# TRS_NANO.net
KiCad netlist of a schematic drawn in EAGLE
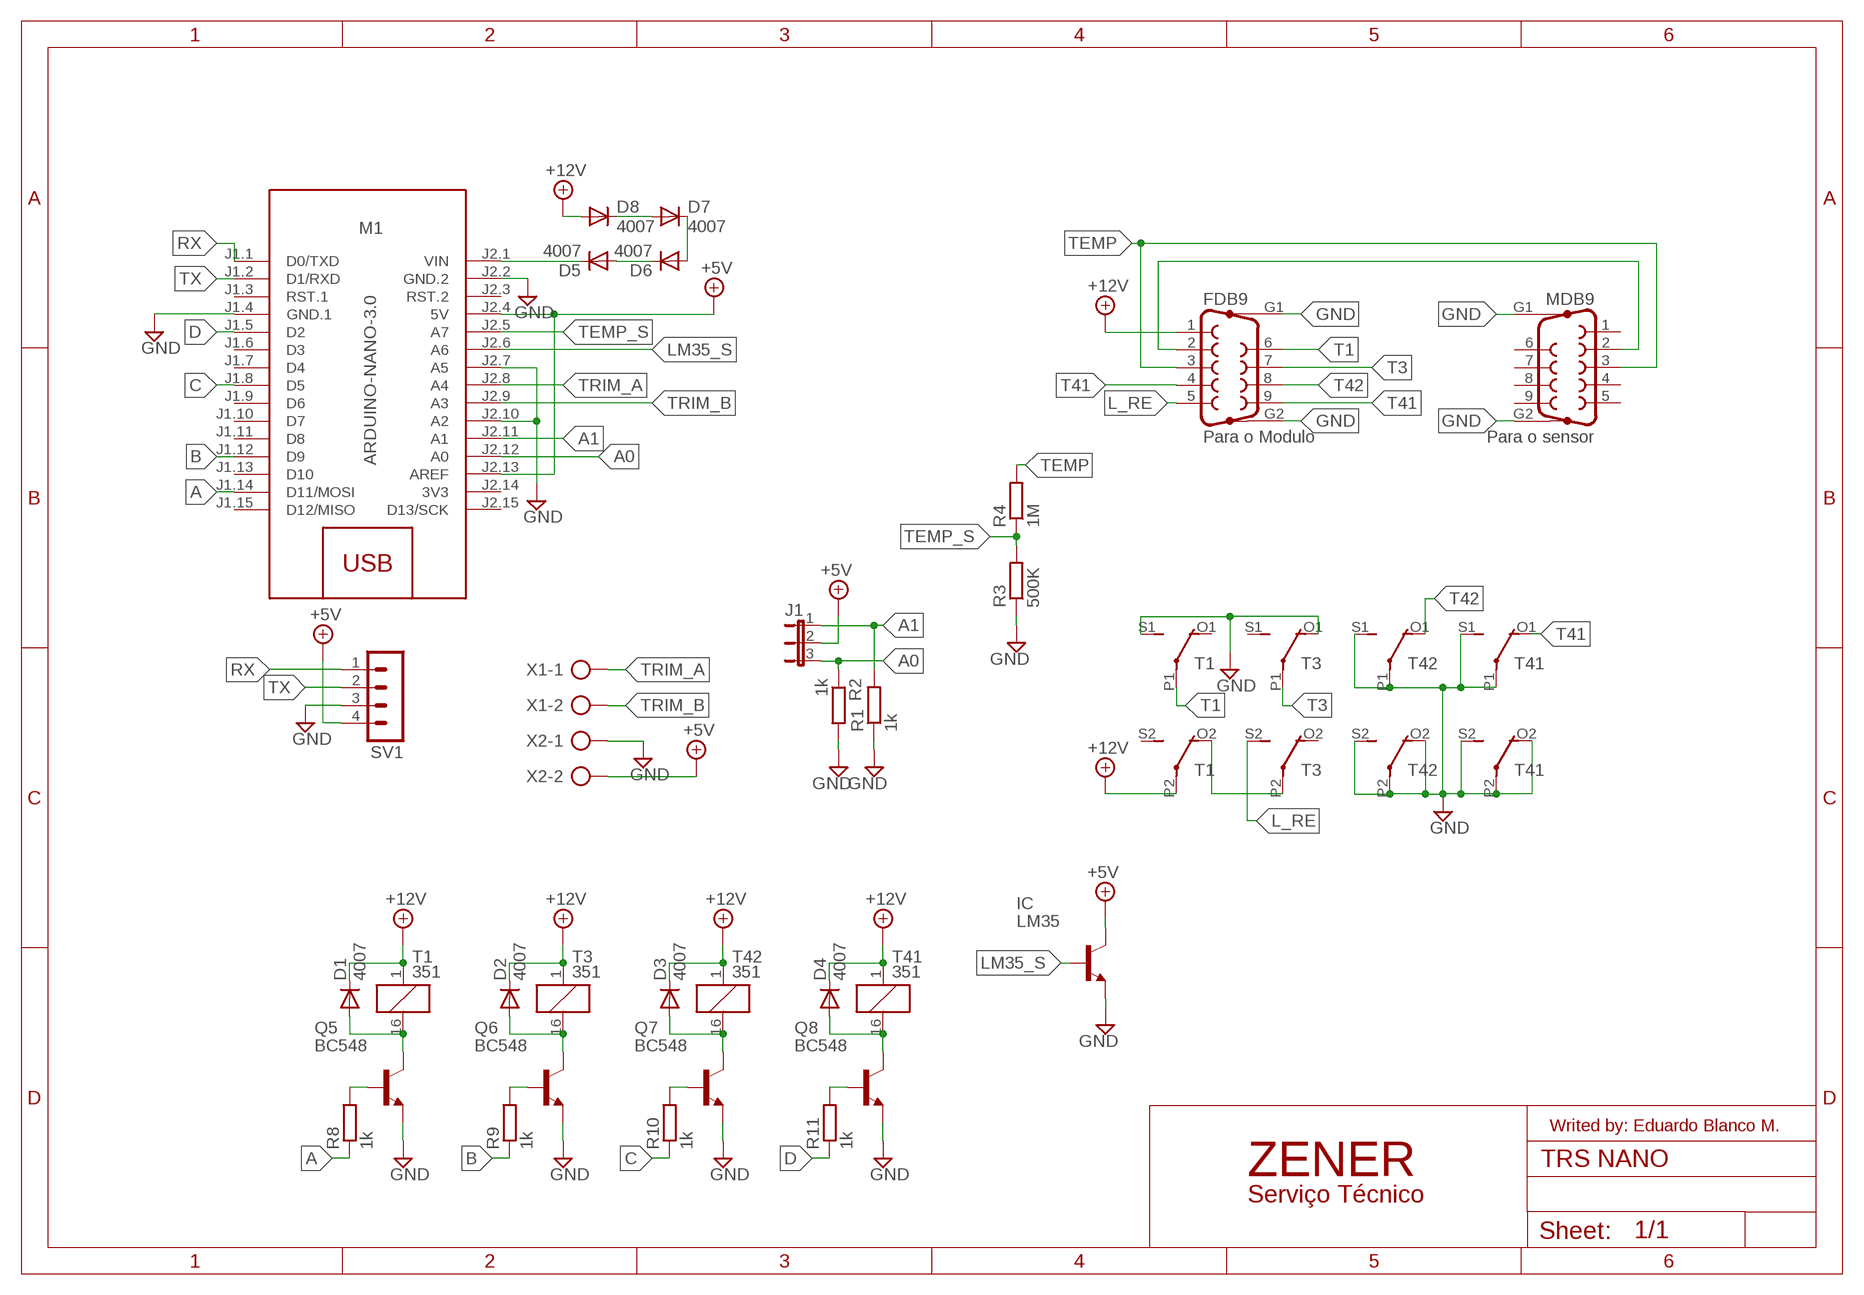
[diagram p0: schematic, sheet 1]

(export (version "E")
  (design (tool "Eeschema 10.0.6"))
  (components
    (comp (ref "D1")
      (value "4007")
      (footprint "eagle-import:D-7.5")
      (libsource (lib "eagle-import") (part "DIODE-D-7.5"))
    )
    (comp (ref "D2")
      (value "4007")
      (footprint "eagle-import:D-7.5")
      (libsource (lib "eagle-import") (part "DIODE-D-7.5"))
    )
    (comp (ref "D3")
      (value "4007")
      (footprint "eagle-import:D-7.5")
      (libsource (lib "eagle-import") (part "DIODE-D-7.5"))
    )
    (comp (ref "D4")
      (value "4007")
      (footprint "eagle-import:D-7.5")
      (libsource (lib "eagle-import") (part "DIODE-D-7.5"))
    )
    (comp (ref "D5")
      (value "4007")
      (footprint "eagle-import:D-7.5")
      (libsource (lib "eagle-import") (part "DIODE-D-7.5"))
    )
    (comp (ref "D6")
      (value "4007")
      (footprint "eagle-import:D-7.5")
      (libsource (lib "eagle-import") (part "DIODE-D-7.5"))
    )
    (comp (ref "D7")
      (value "4007")
      (footprint "eagle-import:D-7.5")
      (libsource (lib "eagle-import") (part "DIODE-D-7.5"))
    )
    (comp (ref "D8")
      (value "4007")
      (footprint "eagle-import:D-7.5")
      (libsource (lib "eagle-import") (part "DIODE-D-7.5"))
    )
    (comp (ref "FDB9")
      (value "Para o Modulo")
      (footprint "eagle-import:F09HP")
      (libsource (lib "eagle-import") (part "F09HP"))
    )
    (comp (ref "IC")
      (value "LM35")
      (footprint "eagle-import:TO92-EBC")
      (libsource (lib "eagle-import") (part "BC548"))
    )
    (comp (ref "J1")
      (value "JP2W")
      (footprint "eagle-import:JP2W")
      (libsource (lib "eagle-import") (part "JP2W"))
    )
    (comp (ref "M1")
      (value "ARDUINO-NANO-3.0")
      (footprint "eagle-import:ARDUINO-NANO-3.0")
      (libsource (lib "eagle-import") (part "ARDUINO-NANO-3.0"))
    )
    (comp (ref "MDB9")
      (value "Para o sensor")
      (footprint "eagle-import:F09HP")
      (libsource (lib "eagle-import") (part "F09HP"))
    )
    (comp (ref "Q5")
      (value "BC548")
      (footprint "eagle-import:TO92-EBC")
      (libsource (lib "eagle-import") (part "BC548"))
    )
    (comp (ref "Q6")
      (value "BC548")
      (footprint "eagle-import:TO92-EBC")
      (libsource (lib "eagle-import") (part "BC548"))
    )
    (comp (ref "Q7")
      (value "BC548")
      (footprint "eagle-import:TO92-EBC")
      (libsource (lib "eagle-import") (part "BC548"))
    )
    (comp (ref "Q8")
      (value "BC548")
      (footprint "eagle-import:TO92-EBC")
      (libsource (lib "eagle-import") (part "BC548"))
    )
    (comp (ref "R1")
      (value "1k")
      (footprint "eagle-import:0207_10")
      (libsource (lib "eagle-import") (part "R-EU_0207/10"))
    )
    (comp (ref "R2")
      (value "1k")
      (footprint "eagle-import:0207_7")
      (libsource (lib "eagle-import") (part "R-EU_0207/7"))
    )
    (comp (ref "R3")
      (value "500K")
      (footprint "eagle-import:0207_7")
      (libsource (lib "eagle-import") (part "R-EU_0207/7"))
    )
    (comp (ref "R4")
      (value "1M")
      (footprint "eagle-import:0207_15")
      (libsource (lib "eagle-import") (part "R-EU_0207/15"))
    )
    (comp (ref "R8")
      (value "1k")
      (footprint "eagle-import:0207_5V")
      (libsource (lib "eagle-import") (part "R-EU_0207/5V"))
    )
    (comp (ref "R9")
      (value "1k")
      (footprint "eagle-import:0207_5V")
      (libsource (lib "eagle-import") (part "R-EU_0207/5V"))
    )
    (comp (ref "R10")
      (value "1k")
      (footprint "eagle-import:0207_5V")
      (libsource (lib "eagle-import") (part "R-EU_0207/5V"))
    )
    (comp (ref "R11")
      (value "1k")
      (footprint "eagle-import:0207_5V")
      (libsource (lib "eagle-import") (part "R-EU_0207/5V"))
    )
    (comp (ref "SV1")
      (value "MA04-1")
      (footprint "eagle-import:MA04-1")
      (libsource (lib "eagle-import") (part "MA04-1"))
    )
    (comp (ref "T1")
      (value "351")
      (footprint "eagle-import:351")
      (libsource (lib "eagle-import") (part "351"))
    )
    (comp (ref "T3")
      (value "351")
      (footprint "eagle-import:351")
      (libsource (lib "eagle-import") (part "351"))
    )
    (comp (ref "T41")
      (value "351")
      (footprint "eagle-import:351")
      (libsource (lib "eagle-import") (part "351"))
    )
    (comp (ref "T42")
      (value "351")
      (footprint "eagle-import:351")
      (libsource (lib "eagle-import") (part "351"))
    )
    (comp (ref "X1")
      (value "AK500/2")
      (footprint "eagle-import:AK500_2")
      (libsource (lib "eagle-import") (part "AK500/2"))
    )
    (comp (ref "X2")
      (value "AK500/2")
      (footprint "eagle-import:AK500_2")
      (libsource (lib "eagle-import") (part "AK500/2"))
    )
  )
  (nets
    (net (code "1") (name "+5V") (class "Default")
      (node (ref "IC") (pin "C") (pinfunction "C_C") (pintype "passive"))
      (node (ref "J1") (pin "2") (pinfunction "2_2") (pintype "passive"))
      (node (ref "M1") (pin "J2.13") (pinfunction "AREF_J2.13") (pintype "bidirectional"))
      (node (ref "M1") (pin "J2.4") (pinfunction "5V_J2.4") (pintype "power_in"))
      (node (ref "SV1") (pin "4") (pinfunction "4_4") (pintype "passive"))
      (node (ref "X2") (pin "2") (pinfunction "KL_2") (pintype "passive"))
    )
    (net (code "2") (name "+12V") (class "Default")
      (node (ref "D1") (pin "C") (pinfunction "C_C") (pintype "passive"))
      (node (ref "D2") (pin "C") (pinfunction "C_C") (pintype "passive"))
      (node (ref "D3") (pin "C") (pinfunction "C_C") (pintype "passive"))
      (node (ref "D4") (pin "C") (pinfunction "C_C") (pintype "passive"))
      (node (ref "D8") (pin "A") (pinfunction "A_A") (pintype "passive"))
      (node (ref "FDB9") (pin "1") (pinfunction "1_1") (pintype "passive"))
      (node (ref "T1") (pin "1") (pinfunction "1_1") (pintype "passive"))
      (node (ref "T1") (pin "P2") (pinfunction "P_P2") (pintype "passive"))
      (node (ref "T3") (pin "1") (pinfunction "1_1") (pintype "passive"))
      (node (ref "T41") (pin "1") (pinfunction "1_1") (pintype "passive"))
      (node (ref "T42") (pin "1") (pinfunction "1_1") (pintype "passive"))
    )
    (net (code "3") (name "/3V3") (class "Default")
      (node (ref "M1") (pin "J2.14") (pinfunction "3V3_J2.14") (pintype "power_in"))
    )
    (net (code "4") (name "A") (class "Default")
      (node (ref "M1") (pin "J1.14") (pinfunction "D11/MOSI_J1.14") (pintype "bidirectional"))
      (node (ref "R8") (pin "1") (pinfunction "1_1") (pintype "passive"))
    )
    (net (code "5") (name "A0") (class "Default")
      (node (ref "J1") (pin "3") (pinfunction "3_3") (pintype "passive"))
      (node (ref "M1") (pin "J2.12") (pinfunction "A0_J2.12") (pintype "bidirectional"))
      (node (ref "R2") (pin "1") (pinfunction "1_1") (pintype "passive"))
    )
    (net (code "6") (name "A1") (class "Default")
      (node (ref "J1") (pin "1") (pinfunction "1_1") (pintype "passive"))
      (node (ref "M1") (pin "J2.11") (pinfunction "A1_J2.11") (pintype "bidirectional"))
      (node (ref "R1") (pin "2") (pinfunction "2_2") (pintype "passive"))
    )
    (net (code "7") (name "B") (class "Default")
      (node (ref "M1") (pin "J1.12") (pinfunction "D9_J1.12") (pintype "bidirectional"))
      (node (ref "R9") (pin "1") (pinfunction "1_1") (pintype "passive"))
    )
    (net (code "8") (name "C") (class "Default")
      (node (ref "M1") (pin "J1.8") (pinfunction "D5_J1.8") (pintype "bidirectional"))
      (node (ref "R10") (pin "1") (pinfunction "1_1") (pintype "passive"))
    )
    (net (code "9") (name "D") (class "Default")
      (node (ref "M1") (pin "J1.5") (pinfunction "D2_J1.5") (pintype "bidirectional"))
      (node (ref "R11") (pin "1") (pinfunction "1_1") (pintype "passive"))
    )
    (net (code "10") (name "GND") (class "Default")
      (node (ref "FDB9") (pin "G1") (pinfunction "G1_G1") (pintype "passive"))
      (node (ref "FDB9") (pin "G2") (pinfunction "G2_G2") (pintype "passive"))
      (node (ref "IC") (pin "E") (pinfunction "E_E") (pintype "passive"))
      (node (ref "M1") (pin "J1.4") (pinfunction "GND.1_J1.4") (pintype "power_in"))
      (node (ref "M1") (pin "J2.10") (pinfunction "A2_J2.10") (pintype "bidirectional"))
      (node (ref "M1") (pin "J2.2") (pinfunction "GND.2_J2.2") (pintype "power_in"))
      (node (ref "M1") (pin "J2.7") (pinfunction "A5_J2.7") (pintype "bidirectional"))
      (node (ref "MDB9") (pin "G1") (pinfunction "G1_G1") (pintype "passive"))
      (node (ref "MDB9") (pin "G2") (pinfunction "G2_G2") (pintype "passive"))
      (node (ref "Q5") (pin "E") (pinfunction "E_E") (pintype "passive"))
      (node (ref "Q6") (pin "E") (pinfunction "E_E") (pintype "passive"))
      (node (ref "Q7") (pin "E") (pinfunction "E_E") (pintype "passive"))
      (node (ref "Q8") (pin "E") (pinfunction "E_E") (pintype "passive"))
      (node (ref "R1") (pin "1") (pinfunction "1_1") (pintype "passive"))
      (node (ref "R2") (pin "2") (pinfunction "2_2") (pintype "passive"))
      (node (ref "R3") (pin "1") (pinfunction "1_1") (pintype "passive"))
      (node (ref "SV1") (pin "3") (pinfunction "3_3") (pintype "passive"))
      (node (ref "T1") (pin "S1") (pinfunction "S_S1") (pintype "passive"))
      (node (ref "T3") (pin "O1") (pinfunction "O_O1") (pintype "passive"))
      (node (ref "T41") (pin "O2") (pinfunction "O_O2") (pintype "passive"))
      (node (ref "T41") (pin "P1") (pinfunction "P_P1") (pintype "passive"))
      (node (ref "T41") (pin "P2") (pinfunction "P_P2") (pintype "passive"))
      (node (ref "T41") (pin "S1") (pinfunction "S_S1") (pintype "passive"))
      (node (ref "T41") (pin "S2") (pinfunction "S_S2") (pintype "passive"))
      (node (ref "T42") (pin "O2") (pinfunction "O_O2") (pintype "passive"))
      (node (ref "T42") (pin "P1") (pinfunction "P_P1") (pintype "passive"))
      (node (ref "T42") (pin "P2") (pinfunction "P_P2") (pintype "passive"))
      (node (ref "T42") (pin "S1") (pinfunction "S_S1") (pintype "passive"))
      (node (ref "T42") (pin "S2") (pinfunction "S_S2") (pintype "passive"))
      (node (ref "X2") (pin "1") (pinfunction "KL_1") (pintype "passive"))
    )
    (net (code "11") (name "LM35_S") (class "Default")
      (node (ref "IC") (pin "B") (pinfunction "B_B") (pintype "passive"))
      (node (ref "M1") (pin "J2.6") (pinfunction "A6_J2.6") (pintype "bidirectional"))
    )
    (net (code "12") (name "L_RE") (class "Default")
      (node (ref "FDB9") (pin "5") (pinfunction "5_5") (pintype "passive"))
      (node (ref "T3") (pin "S2") (pinfunction "S_S2") (pintype "passive"))
    )
    (net (code "13") (name "Net-(D5-PadA)") (class "Default")
      (node (ref "D5") (pin "A") (pinfunction "A_A") (pintype "passive"))
      (node (ref "D6") (pin "C") (pinfunction "C_C") (pintype "passive"))
    )
    (net (code "14") (name "Net-(D6-PadA)") (class "Default")
      (node (ref "D6") (pin "A") (pinfunction "A_A") (pintype "passive"))
      (node (ref "D7") (pin "C") (pinfunction "C_C") (pintype "passive"))
    )
    (net (code "15") (name "Net-(D7-PadA)") (class "Default")
      (node (ref "D7") (pin "A") (pinfunction "A_A") (pintype "passive"))
      (node (ref "D8") (pin "C") (pinfunction "C_C") (pintype "passive"))
    )
    (net (code "16") (name "Net-(FDB9-Pad2)") (class "Default")
      (node (ref "FDB9") (pin "2") (pinfunction "2_2") (pintype "passive"))
      (node (ref "MDB9") (pin "2") (pinfunction "2_2") (pintype "passive"))
    )
    (net (code "17") (name "Net-(M1-VIN)") (class "Default")
      (node (ref "D5") (pin "C") (pinfunction "C_C") (pintype "passive"))
      (node (ref "M1") (pin "J2.1") (pinfunction "VIN_J2.1") (pintype "power_in"))
    )
    (net (code "18") (name "Net-(Q5-PadB)") (class "Default")
      (node (ref "Q5") (pin "B") (pinfunction "B_B") (pintype "passive"))
      (node (ref "R8") (pin "2") (pinfunction "2_2") (pintype "passive"))
    )
    (net (code "19") (name "Net-(Q6-PadB)") (class "Default")
      (node (ref "Q6") (pin "B") (pinfunction "B_B") (pintype "passive"))
      (node (ref "R9") (pin "2") (pinfunction "2_2") (pintype "passive"))
    )
    (net (code "20") (name "Net-(Q7-PadB)") (class "Default")
      (node (ref "Q7") (pin "B") (pinfunction "B_B") (pintype "passive"))
      (node (ref "R10") (pin "2") (pinfunction "2_2") (pintype "passive"))
    )
    (net (code "21") (name "Net-(Q8-PadB)") (class "Default")
      (node (ref "Q8") (pin "B") (pinfunction "B_B") (pintype "passive"))
      (node (ref "R11") (pin "2") (pinfunction "2_2") (pintype "passive"))
    )
    (net (code "22") (name "Net-(T1A-2)") (class "Default")
      (node (ref "D1") (pin "A") (pinfunction "A_A") (pintype "passive"))
      (node (ref "Q5") (pin "C") (pinfunction "C_C") (pintype "passive"))
      (node (ref "T1") (pin "16") (pinfunction "2_16") (pintype "passive"))
    )
    (net (code "23") (name "Net-(T1C-O)") (class "Default")
      (node (ref "T1") (pin "O2") (pinfunction "O_O2") (pintype "passive"))
      (node (ref "T3") (pin "P2") (pinfunction "P_P2") (pintype "passive"))
    )
    (net (code "24") (name "Net-(T3A-2)") (class "Default")
      (node (ref "D2") (pin "A") (pinfunction "A_A") (pintype "passive"))
      (node (ref "Q6") (pin "C") (pinfunction "C_C") (pintype "passive"))
      (node (ref "T3") (pin "16") (pinfunction "2_16") (pintype "passive"))
    )
    (net (code "25") (name "Net-(T41A-2)") (class "Default")
      (node (ref "D4") (pin "A") (pinfunction "A_A") (pintype "passive"))
      (node (ref "Q8") (pin "C") (pinfunction "C_C") (pintype "passive"))
      (node (ref "T41") (pin "16") (pinfunction "2_16") (pintype "passive"))
    )
    (net (code "26") (name "Net-(T42A-2)") (class "Default")
      (node (ref "D3") (pin "A") (pinfunction "A_A") (pintype "passive"))
      (node (ref "Q7") (pin "C") (pinfunction "C_C") (pintype "passive"))
      (node (ref "T42") (pin "16") (pinfunction "2_16") (pintype "passive"))
    )
    (net (code "27") (name "RX") (class "Default")
      (node (ref "M1") (pin "J1.1") (pinfunction "D0/TXD_J1.1") (pintype "bidirectional"))
      (node (ref "SV1") (pin "1") (pinfunction "1_1") (pintype "passive"))
    )
    (net (code "28") (name "T1") (class "Default")
      (node (ref "FDB9") (pin "6") (pinfunction "6_6") (pintype "passive"))
      (node (ref "T1") (pin "P1") (pinfunction "P_P1") (pintype "passive"))
    )
    (net (code "29") (name "T3") (class "Default")
      (node (ref "FDB9") (pin "7") (pinfunction "7_7") (pintype "passive"))
      (node (ref "T3") (pin "P1") (pinfunction "P_P1") (pintype "passive"))
    )
    (net (code "30") (name "T41") (class "Default")
      (node (ref "FDB9") (pin "4") (pinfunction "4_4") (pintype "passive"))
      (node (ref "FDB9") (pin "9") (pinfunction "9_9") (pintype "passive"))
      (node (ref "T41") (pin "O1") (pinfunction "O_O1") (pintype "passive"))
    )
    (net (code "31") (name "T42") (class "Default")
      (node (ref "FDB9") (pin "8") (pinfunction "8_8") (pintype "passive"))
      (node (ref "T42") (pin "O1") (pinfunction "O_O1") (pintype "passive"))
    )
    (net (code "32") (name "TEMP") (class "Default")
      (node (ref "FDB9") (pin "3") (pinfunction "3_3") (pintype "passive"))
      (node (ref "MDB9") (pin "3") (pinfunction "3_3") (pintype "passive"))
      (node (ref "R4") (pin "2") (pinfunction "2_2") (pintype "passive"))
    )
    (net (code "33") (name "TEMP_S") (class "Default")
      (node (ref "M1") (pin "J2.5") (pinfunction "A7_J2.5") (pintype "bidirectional"))
      (node (ref "R3") (pin "2") (pinfunction "2_2") (pintype "passive"))
      (node (ref "R4") (pin "1") (pinfunction "1_1") (pintype "passive"))
    )
    (net (code "34") (name "TRIM_A") (class "Default")
      (node (ref "M1") (pin "J2.8") (pinfunction "A4_J2.8") (pintype "bidirectional"))
      (node (ref "X1") (pin "1") (pinfunction "KL_1") (pintype "passive"))
    )
    (net (code "35") (name "TRIM_B") (class "Default")
      (node (ref "M1") (pin "J2.9") (pinfunction "A3_J2.9") (pintype "bidirectional"))
      (node (ref "X1") (pin "2") (pinfunction "KL_2") (pintype "passive"))
    )
    (net (code "36") (name "TX") (class "Default")
      (node (ref "M1") (pin "J1.2") (pinfunction "D1/RXD_J1.2") (pintype "bidirectional"))
      (node (ref "SV1") (pin "2") (pinfunction "2_2") (pintype "passive"))
    )
    (net (code "37") (name "unconnected-(M1-D3-PadJ1.6)") (class "Default")
      (node (ref "M1") (pin "J1.6") (pinfunction "D3_J1.6") (pintype "bidirectional"))
    )
    (net (code "38") (name "unconnected-(M1-D4-PadJ1.7)") (class "Default")
      (node (ref "M1") (pin "J1.7") (pinfunction "D4_J1.7") (pintype "bidirectional"))
    )
    (net (code "39") (name "unconnected-(M1-D6-PadJ1.9)") (class "Default")
      (node (ref "M1") (pin "J1.9") (pinfunction "D6_J1.9") (pintype "bidirectional"))
    )
    (net (code "40") (name "unconnected-(M1-D7-PadJ1.10)") (class "Default")
      (node (ref "M1") (pin "J1.10") (pinfunction "D7_J1.10") (pintype "bidirectional"))
    )
    (net (code "41") (name "unconnected-(M1-D8-PadJ1.11)") (class "Default")
      (node (ref "M1") (pin "J1.11") (pinfunction "D8_J1.11") (pintype "bidirectional"))
    )
    (net (code "42") (name "unconnected-(M1-D10-PadJ1.13)") (class "Default")
      (node (ref "M1") (pin "J1.13") (pinfunction "D10_J1.13") (pintype "bidirectional"))
    )
    (net (code "43") (name "unconnected-(M1-D12{slash}MISO-PadJ1.15)") (class "Default")
      (node (ref "M1") (pin "J1.15") (pinfunction "D12/MISO_J1.15") (pintype "bidirectional"))
    )
    (net (code "44") (name "unconnected-(M1-D13{slash}SCK-PadJ2.15)") (class "Default")
      (node (ref "M1") (pin "J2.15") (pinfunction "D13/SCK_J2.15") (pintype "bidirectional"))
    )
    (net (code "45") (name "unconnected-(M1-RST.1-PadJ1.3)") (class "Default")
      (node (ref "M1") (pin "J1.3") (pinfunction "RST.1_J1.3") (pintype "bidirectional"))
    )
    (net (code "46") (name "unconnected-(M1-RST.2-PadJ2.3)") (class "Default")
      (node (ref "M1") (pin "J2.3") (pinfunction "RST.2_J2.3") (pintype "bidirectional"))
    )
    (net (code "47") (name "unconnected-(MDB9-Pad1)") (class "Default")
      (node (ref "MDB9") (pin "1") (pinfunction "1_1") (pintype "passive"))
    )
    (net (code "48") (name "unconnected-(MDB9-Pad4)") (class "Default")
      (node (ref "MDB9") (pin "4") (pinfunction "4_4") (pintype "passive"))
    )
    (net (code "49") (name "unconnected-(MDB9-Pad5)") (class "Default")
      (node (ref "MDB9") (pin "5") (pinfunction "5_5") (pintype "passive"))
    )
    (net (code "50") (name "unconnected-(MDB9-Pad6)") (class "Default")
      (node (ref "MDB9") (pin "6") (pinfunction "6_6") (pintype "passive"))
    )
    (net (code "51") (name "unconnected-(MDB9-Pad7)") (class "Default")
      (node (ref "MDB9") (pin "7") (pinfunction "7_7") (pintype "passive"))
    )
    (net (code "52") (name "unconnected-(MDB9-Pad8)") (class "Default")
      (node (ref "MDB9") (pin "8") (pinfunction "8_8") (pintype "passive"))
    )
    (net (code "53") (name "unconnected-(MDB9-Pad9)") (class "Default")
      (node (ref "MDB9") (pin "9") (pinfunction "9_9") (pintype "passive"))
    )
    (net (code "54") (name "unconnected-(T1B-O-PadO1)") (class "Default")
      (node (ref "T1") (pin "O1") (pinfunction "O_O1") (pintype "passive"))
    )
    (net (code "55") (name "unconnected-(T1C-S-PadS2)") (class "Default")
      (node (ref "T1") (pin "S2") (pinfunction "S_S2") (pintype "passive"))
    )
    (net (code "56") (name "unconnected-(T3B-S-PadS1)") (class "Default")
      (node (ref "T3") (pin "S1") (pinfunction "S_S1") (pintype "passive"))
    )
    (net (code "57") (name "unconnected-(T3C-O-PadO2)") (class "Default")
      (node (ref "T3") (pin "O2") (pinfunction "O_O2") (pintype "passive"))
    )
  )
)
